# esp12Sensors.net
KiCad netlist of a schematic drawn in EAGLE
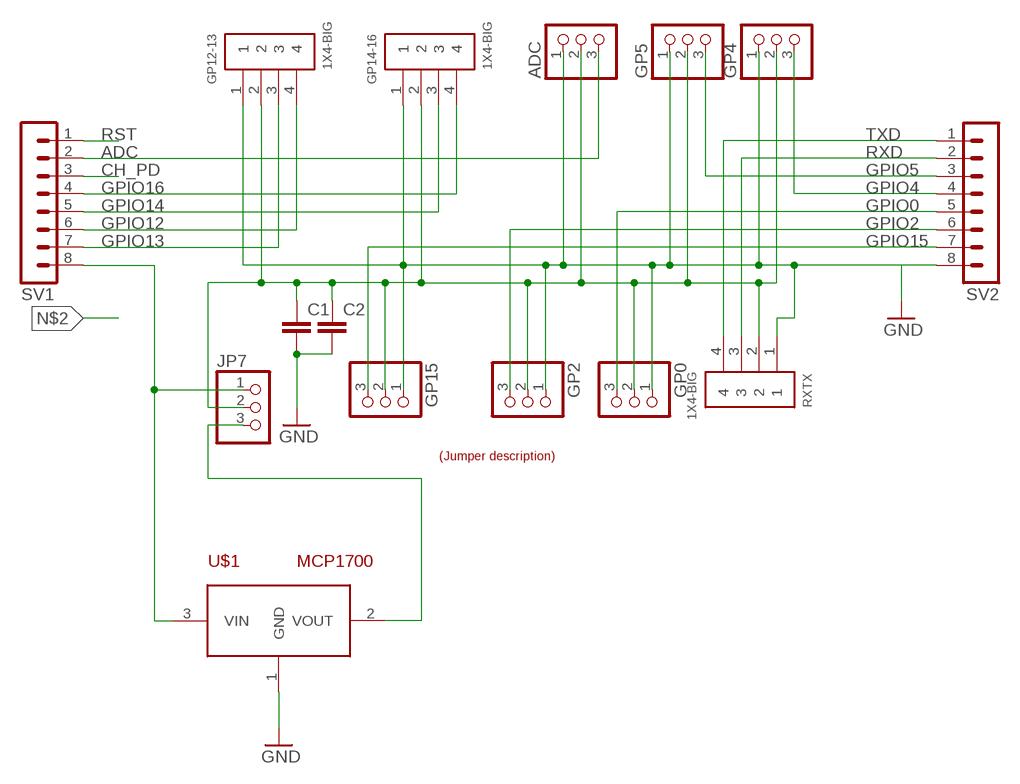
[diagram p0: schematic, sheet 1]

(export (version "E")
  (design (tool "Eeschema 10.0.6"))
  (components
    (comp (ref "ADC")
      (value "PINHD-1X3")
      (footprint "eagle-import:1X03")
      (libsource (lib "eagle-import") (part "PINHD-1X3"))
    )
    (comp (ref "C1")
      (value "C-EUC0805")
      (footprint "eagle-import:C0805")
      (libsource (lib "eagle-import") (part "C-EUC0805"))
    )
    (comp (ref "C2")
      (value "C-EUC0805")
      (footprint "eagle-import:C0805")
      (libsource (lib "eagle-import") (part "C-EUC0805"))
    )
    (comp (ref "GP0")
      (value "PINHD-1X3")
      (footprint "eagle-import:1X03")
      (libsource (lib "eagle-import") (part "PINHD-1X3"))
    )
    (comp (ref "GP2")
      (value "PINHD-1X3")
      (footprint "eagle-import:1X03")
      (libsource (lib "eagle-import") (part "PINHD-1X3"))
    )
    (comp (ref "GP4")
      (value "PINHD-1X3")
      (footprint "eagle-import:1X03")
      (libsource (lib "eagle-import") (part "PINHD-1X3"))
    )
    (comp (ref "GP5")
      (value "PINHD-1X3")
      (footprint "eagle-import:1X03")
      (libsource (lib "eagle-import") (part "PINHD-1X3"))
    )
    (comp (ref "GP12-13")
      (value "1X4-BIG")
      (footprint "eagle-import:1X04-BIG")
      (libsource (lib "eagle-import") (part "1X4-BIG"))
    )
    (comp (ref "GP14-16")
      (value "1X4-BIG")
      (footprint "eagle-import:1X04-BIG")
      (libsource (lib "eagle-import") (part "1X4-BIG"))
    )
    (comp (ref "GP15")
      (value "PINHD-1X3")
      (footprint "eagle-import:1X03")
      (libsource (lib "eagle-import") (part "PINHD-1X3"))
    )
    (comp (ref "JP7")
      (value "PINHD-1X3")
      (footprint "eagle-import:1X03")
      (libsource (lib "eagle-import") (part "PINHD-1X3"))
    )
    (comp (ref "RXTX")
      (value "1X4-BIG")
      (footprint "eagle-import:1X04-BIG")
      (libsource (lib "eagle-import") (part "1X4-BIG"))
    )
    (comp (ref "SV1")
      (value "MA08-1")
      (footprint "eagle-import:MA08-1")
      (libsource (lib "eagle-import") (part "MA08-1"))
    )
    (comp (ref "SV2")
      (value "MA08-1")
      (footprint "eagle-import:MA08-1")
      (libsource (lib "eagle-import") (part "MA08-1"))
    )
    (comp (ref "U$1")
      (value "MCP1700")
      (footprint "eagle-import:SOT-23")
      (libsource (lib "eagle-import") (part "MCP1700"))
    )
    (comp (ref "U$2")
      (value "LABEL_JUMPER_1X3")
      (footprint "eagle-import:JUMP3_DESC")
      (fields (field (name "LEFT") "5V") (field (name "RIGHT") "3V3"))
      (libsource (lib "eagle-import") (part "LABEL_JUMPER_1X3"))
    )
  )
  (nets
    (net (code "1") (name "/ADC") (class "Default")
      (node (ref "ADC") (pin "3") (pinfunction "3_3") (pintype "passive"))
      (node (ref "SV1") (pin "2") (pinfunction "2_2") (pintype "passive"))
    )
    (net (code "2") (name "/CH_PD") (class "Default")
      (node (ref "SV1") (pin "3") (pinfunction "3_3") (pintype "passive"))
    )
    (net (code "3") (name "/GPIO0") (class "Default")
      (node (ref "GP0") (pin "3") (pinfunction "3_3") (pintype "passive"))
      (node (ref "SV2") (pin "5") (pinfunction "5_5") (pintype "passive"))
    )
    (net (code "4") (name "/GPIO2") (class "Default")
      (node (ref "GP2") (pin "3") (pinfunction "3_3") (pintype "passive"))
      (node (ref "SV2") (pin "6") (pinfunction "6_6") (pintype "passive"))
    )
    (net (code "5") (name "/GPIO4") (class "Default")
      (node (ref "GP4") (pin "3") (pinfunction "3_3") (pintype "passive"))
      (node (ref "SV2") (pin "4") (pinfunction "4_4") (pintype "passive"))
    )
    (net (code "6") (name "/GPIO5") (class "Default")
      (node (ref "GP5") (pin "3") (pinfunction "3_3") (pintype "passive"))
      (node (ref "SV2") (pin "3") (pinfunction "3_3") (pintype "passive"))
    )
    (net (code "7") (name "/GPIO12") (class "Default")
      (node (ref "GP12-13") (pin "3") (pinfunction "3_3") (pintype "bidirectional"))
      (node (ref "SV1") (pin "7") (pinfunction "7_7") (pintype "passive"))
    )
    (net (code "8") (name "/GPIO13") (class "Default")
      (node (ref "GP12-13") (pin "4") (pinfunction "4_4") (pintype "bidirectional"))
      (node (ref "SV1") (pin "6") (pinfunction "6_6") (pintype "passive"))
    )
    (net (code "9") (name "/GPIO14") (class "Default")
      (node (ref "GP14-16") (pin "3") (pinfunction "3_3") (pintype "bidirectional"))
      (node (ref "SV1") (pin "5") (pinfunction "5_5") (pintype "passive"))
    )
    (net (code "10") (name "/GPIO15") (class "Default")
      (node (ref "GP15") (pin "3") (pinfunction "3_3") (pintype "passive"))
      (node (ref "SV2") (pin "7") (pinfunction "7_7") (pintype "passive"))
    )
    (net (code "11") (name "/GPIO16") (class "Default")
      (node (ref "GP14-16") (pin "4") (pinfunction "4_4") (pintype "bidirectional"))
      (node (ref "SV1") (pin "4") (pinfunction "4_4") (pintype "passive"))
    )
    (net (code "12") (name "/RST") (class "Default")
      (node (ref "SV1") (pin "1") (pinfunction "1_1") (pintype "passive"))
    )
    (net (code "13") (name "/RXD") (class "Default")
      (node (ref "RXTX") (pin "3") (pinfunction "3_3") (pintype "bidirectional"))
      (node (ref "SV2") (pin "2") (pinfunction "2_2") (pintype "passive"))
    )
    (net (code "14") (name "/TXD") (class "Default")
      (node (ref "RXTX") (pin "4") (pinfunction "4_4") (pintype "bidirectional"))
      (node (ref "SV2") (pin "1") (pinfunction "1_1") (pintype "passive"))
    )
    (net (code "15") (name "GND") (class "Default")
      (node (ref "ADC") (pin "1") (pinfunction "1_1") (pintype "passive"))
      (node (ref "C1") (pin "2") (pinfunction "2_2") (pintype "passive"))
      (node (ref "C2") (pin "2") (pinfunction "2_2") (pintype "passive"))
      (node (ref "GP0") (pin "1") (pinfunction "1_1") (pintype "passive"))
      (node (ref "GP12-13") (pin "1") (pinfunction "1_1") (pintype "bidirectional"))
      (node (ref "GP14-16") (pin "1") (pinfunction "1_1") (pintype "bidirectional"))
      (node (ref "GP15") (pin "1") (pinfunction "1_1") (pintype "passive"))
      (node (ref "GP2") (pin "1") (pinfunction "1_1") (pintype "passive"))
      (node (ref "GP4") (pin "1") (pinfunction "1_1") (pintype "passive"))
      (node (ref "GP5") (pin "1") (pinfunction "1_1") (pintype "passive"))
      (node (ref "RXTX") (pin "1") (pinfunction "1_1") (pintype "bidirectional"))
      (node (ref "SV2") (pin "8") (pinfunction "8_8") (pintype "passive"))
      (node (ref "U$1") (pin "1") (pinfunction "GND_1") (pintype "bidirectional"))
    )
    (net (code "17") (name "Net-(ADC-Pad2)") (class "Default")
      (node (ref "ADC") (pin "2") (pinfunction "2_2") (pintype "passive"))
      (node (ref "C1") (pin "1") (pinfunction "1_1") (pintype "passive"))
      (node (ref "C2") (pin "1") (pinfunction "1_1") (pintype "passive"))
      (node (ref "GP0") (pin "2") (pinfunction "2_2") (pintype "passive"))
      (node (ref "GP12-13") (pin "2") (pinfunction "2_2") (pintype "bidirectional"))
      (node (ref "GP14-16") (pin "2") (pinfunction "2_2") (pintype "bidirectional"))
      (node (ref "GP15") (pin "2") (pinfunction "2_2") (pintype "passive"))
      (node (ref "GP2") (pin "2") (pinfunction "2_2") (pintype "passive"))
      (node (ref "GP4") (pin "2") (pinfunction "2_2") (pintype "passive"))
      (node (ref "GP5") (pin "2") (pinfunction "2_2") (pintype "passive"))
      (node (ref "JP7") (pin "2") (pinfunction "2_2") (pintype "passive"))
      (node (ref "RXTX") (pin "2") (pinfunction "2_2") (pintype "bidirectional"))
    )
    (net (code "18") (name "Net-(U$1-VIN)") (class "Default")
      (node (ref "JP7") (pin "1") (pinfunction "1_1") (pintype "passive"))
      (node (ref "SV1") (pin "8") (pinfunction "8_8") (pintype "passive"))
      (node (ref "U$1") (pin "3") (pinfunction "VIN_3") (pintype "bidirectional"))
    )
    (net (code "19") (name "Net-(U$1-VOUT)") (class "Default")
      (node (ref "JP7") (pin "3") (pinfunction "3_3") (pintype "passive"))
      (node (ref "U$1") (pin "2") (pinfunction "VOUT_2") (pintype "bidirectional"))
    )
  )
)
